# buck1.net
KiCad netlist of a schematic drawn in EAGLE
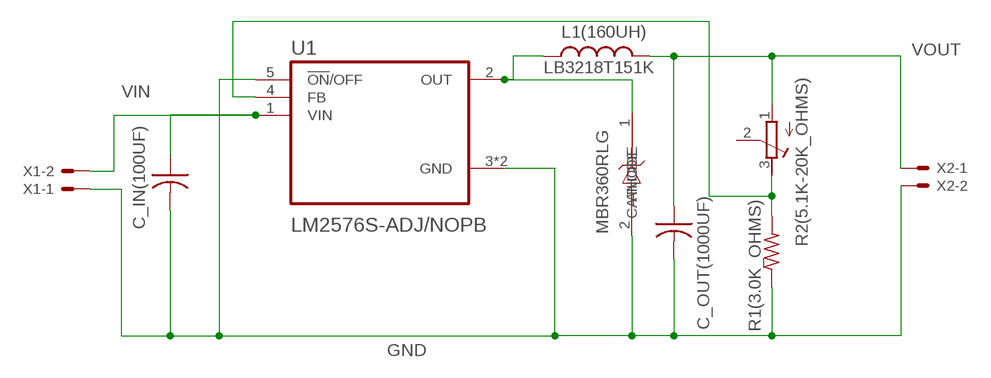
[diagram p0: schematic, sheet 1]

(export (version "E")
  (design (tool "Eeschema 10.0.6"))
  (components
    (comp (ref "CR1")
      (value "MBR360RLG")
      (footprint "eagle-import:DO-201AD_ONS")
      (fields (field (name "MANUFACTURER_PART_NUMBER") "MBR360RLG"))
      (libsource (lib "eagle-import") (part "MBR360RLG"))
    )
    (comp (ref "C_IN(100UF)")
      (value "C-USC1206")
      (footprint "eagle-import:C1206")
      (libsource (lib "eagle-import") (part "C-USC1206"))
    )
    (comp (ref "C_OUT(1000UF)")
      (value "C-USC1206")
      (footprint "eagle-import:C1206")
      (libsource (lib "eagle-import") (part "C-USC1206"))
    )
    (comp (ref "L1(160UH)")
      (value "LB3218T151K")
      (footprint "eagle-import:INDC3218X200N")
      (fields (field (name "DIGI-KEY_PART_NUMBER") "587-3081-1-ND") (field (name "MF") "Taiyo Yuden"))
      (libsource (lib "eagle-import") (part "LB3218T151K"))
    )
    (comp (ref "R1(3.0K_OHMS)")
      (value "R-US_R1206")
      (footprint "eagle-import:R1206")
      (fields (field (name "SPICEPREFIX") "3.0k"))
      (libsource (lib "eagle-import") (part "R-US_R1206"))
    )
    (comp (ref "R2(5.1K-20K_OHMS)")
      (value "R-TRIMMTS63Z")
      (footprint "eagle-import:RTRIMTS63Z")
      (libsource (lib "eagle-import") (part "R-TRIMMTS63Z"))
    )
    (comp (ref "U1")
      (value "LM2576S-ADJ/NOPB")
      (footprint "eagle-import:VREG_TPS79625KTTR")
      (fields
        (field (name "DIGI-KEY_PART_NUMBER") "LM2576S-ADJ/NOPB-ND")
        (field (name "MF") "Texas Instruments")
      )
      (libsource (lib "eagle-import") (part "LM2576S-ADJ/NOPB"))
    )
    (comp (ref "X1")
      (value "22-23-2021")
      (footprint "eagle-import:22-23-2021")
      (fields (field (name "MF") "MOLEX"))
      (libsource (lib "eagle-import") (part "22-23-2021"))
    )
    (comp (ref "X2")
      (value "22-23-2021")
      (footprint "eagle-import:22-23-2021")
      (fields (field (name "MF") "MOLEX"))
      (libsource (lib "eagle-import") (part "22-23-2021"))
    )
  )
  (nets
    (net (code "1") (name "/GND") (class "Default")
      (node (ref "CR1") (pin "2") (pinfunction "ANODE_2") (pintype "passive"))
      (node (ref "C_IN(100UF)") (pin "2") (pinfunction "2_2") (pintype "passive"))
      (node (ref "C_OUT(1000UF)") (pin "2") (pinfunction "2_2") (pintype "passive"))
      (node (ref "R1(3.0K_OHMS)") (pin "1") (pinfunction "1_1") (pintype "passive"))
      (node (ref "U1") (pin "3") (pinfunction "GND_3") (pintype "power_in"))
      (node (ref "U1") (pin "5") (pinfunction "~{ON}/OFF_5") (pintype "input"))
      (node (ref "U1") (pin "6") (pinfunction "GND_6") (pintype "power_in"))
      (node (ref "X1") (pin "1") (pinfunction "S_1") (pintype "passive"))
      (node (ref "X2") (pin "2") (pinfunction "S_2") (pintype "passive"))
    )
    (net (code "2") (name "/VIN") (class "Default")
      (node (ref "C_IN(100UF)") (pin "1") (pinfunction "1_1") (pintype "passive"))
      (node (ref "U1") (pin "1") (pinfunction "VIN_1") (pintype "input"))
      (node (ref "X1") (pin "2") (pinfunction "S_2") (pintype "passive"))
    )
    (net (code "3") (name "/VOUT") (class "Default")
      (node (ref "C_OUT(1000UF)") (pin "1") (pinfunction "1_1") (pintype "passive"))
      (node (ref "L1(160UH)") (pin "2") (pinfunction "2_2") (pintype "passive"))
      (node (ref "R2(5.1K-20K_OHMS)") (pin "1") (pinfunction "A_1") (pintype "passive"))
      (node (ref "X2") (pin "1") (pinfunction "S_1") (pintype "passive"))
    )
    (net (code "4") (name "Net-(CR1-CATHODE)") (class "Default")
      (node (ref "CR1") (pin "1") (pinfunction "CATHODE_1") (pintype "passive"))
      (node (ref "L1(160UH)") (pin "1") (pinfunction "1_1") (pintype "passive"))
      (node (ref "U1") (pin "2") (pinfunction "OUT_2") (pintype "output"))
    )
    (net (code "5") (name "Net-(R2(5.1K-20K_OHMS)-E)") (class "Default")
      (node (ref "R1(3.0K_OHMS)") (pin "2") (pinfunction "2_2") (pintype "passive"))
      (node (ref "R2(5.1K-20K_OHMS)") (pin "3") (pinfunction "E_3") (pintype "passive"))
      (node (ref "U1") (pin "4") (pinfunction "FB_4") (pintype "input"))
    )
    (net (code "6") (name "unconnected-(R2(5.1K-20K_OHMS)-S-Pad2)") (class "Default")
      (node (ref "R2(5.1K-20K_OHMS)") (pin "2") (pinfunction "S_2") (pintype "passive"))
    )
  )
)
